# VoltageRegulator5V.net
KiCad netlist of a schematic drawn in Altium Designer
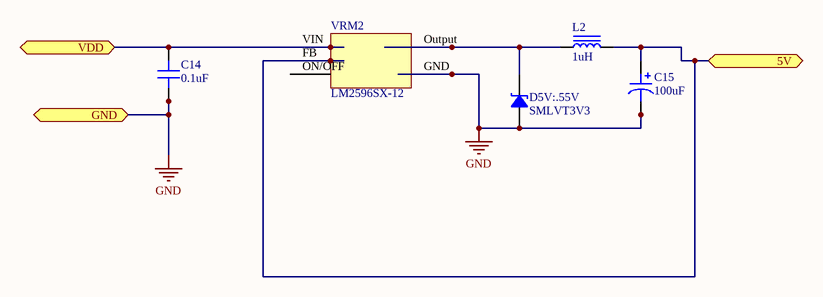
[diagram p0: VoltageRegulator5V.schdoc]

(export (version "E")
  (design (tool "Eeschema 10.0.6"))
  (components
    (comp (ref "C14")
      (value "0.1uF")
      (footprint "CAP 0402/1005")
      (description "CAP CER 0.1UF 16V X7R 0402")
      (fields
        (field (name "PART NUMBER") "C1005X7R1C104K050BC")
        (field (name "MANUFACTURER") "TDK Corporation")
      )
      (libsource (lib "Celestial Library Database") (part "Capacitor"))
    )
    (comp (ref "C15")
      (value "100uF")
      (footprint "CAP ALUM 6.6MM")
      (description "CAP POLYMER 100UF 20% 16V SMD")
      (fields
        (field (name "PART NUMBER") "16SVPC100M")
        (field (name "MANUFACTURER") "Panasonic Electronic Components")
      )
      (libsource (lib "Celestial Library Database") (part "Polarised Capacitor"))
    )
    (comp (ref "D5V:.55V")
      (value "SMLVT3V3")
      (footprint "ST DO214AA SMB")
      (description "TVS DIODE 3.3VWM 10.3VC SMB")
      (fields (field (name "MANUFACTURER") "STMicroelectronics"))
      (libsource (lib "Celestial Library Database") (part "Diode Zener"))
    )
    (comp (ref "L2")
      (value "1uH")
      (footprint "TDK VLS252010CX")
      (description "FIXED IND 1UH 2.29A 65 MOHM SMD")
      (fields (field (name "PART NUMBER") "VLS252010CX-1R0M") (field (name "MANUFACTURER") "TDK Corporation"))
      (libsource (lib "Celestial Library Database") (part "Inductor"))
    )
    (comp (ref "VRM2")
      (value "LM2596SX-12")
      (footprint "DPAK170P1418X200-6L")
      (libsource (lib "Schlib2") (part "LM2596SX-12"))
    )
  )
  (nets
    (net (code "1") (name "/5V") (class "Default")
      (node (ref "C15") (pin "1") (pinfunction "1_1") (pintype "passive"))
      (node (ref "L2") (pin "2") (pinfunction "2_2") (pintype "passive"))
      (node (ref "VRM2") (pin "FB") (pinfunction "*_FB") (pintype "passive"))
    )
    (net (code "2") (name "/VDD") (class "Default")
      (node (ref "C14") (pin "2") (pinfunction "2_2") (pintype "passive"))
      (node (ref "VRM2") (pin "VIN") (pinfunction "Vin_VIN") (pintype "passive"))
    )
    (net (code "3") (name "GND") (class "Default")
      (node (ref "C14") (pin "1") (pinfunction "1_1") (pintype "passive"))
      (node (ref "C15") (pin "2") (pinfunction "2_2") (pintype "passive"))
      (node (ref "D5V:.55V") (pin "1") (pinfunction "1_1") (pintype "passive"))
      (node (ref "VRM2") (pin "GND") (pinfunction "*_GND") (pintype "passive"))
    )
    (net (code "4") (name "Net-(D5V:.55V-Pad2)") (class "Default")
      (node (ref "D5V:.55V") (pin "2") (pinfunction "2_2") (pintype "passive"))
      (node (ref "L2") (pin "1") (pinfunction "1_1") (pintype "passive"))
      (node (ref "VRM2") (pin "Output") (pinfunction "*_Output") (pintype "passive"))
    )
    (net (code "5") (name "unconnected-(VRM2-*-PadON{slash}OFF)") (class "Default")
      (node (ref "VRM2") (pin "ON/OFF") (pinfunction "*_ON/OFF") (pintype "passive"))
    )
  )
)
